# blues-hardware.net
KiCad netlist of a schematic drawn in EAGLE
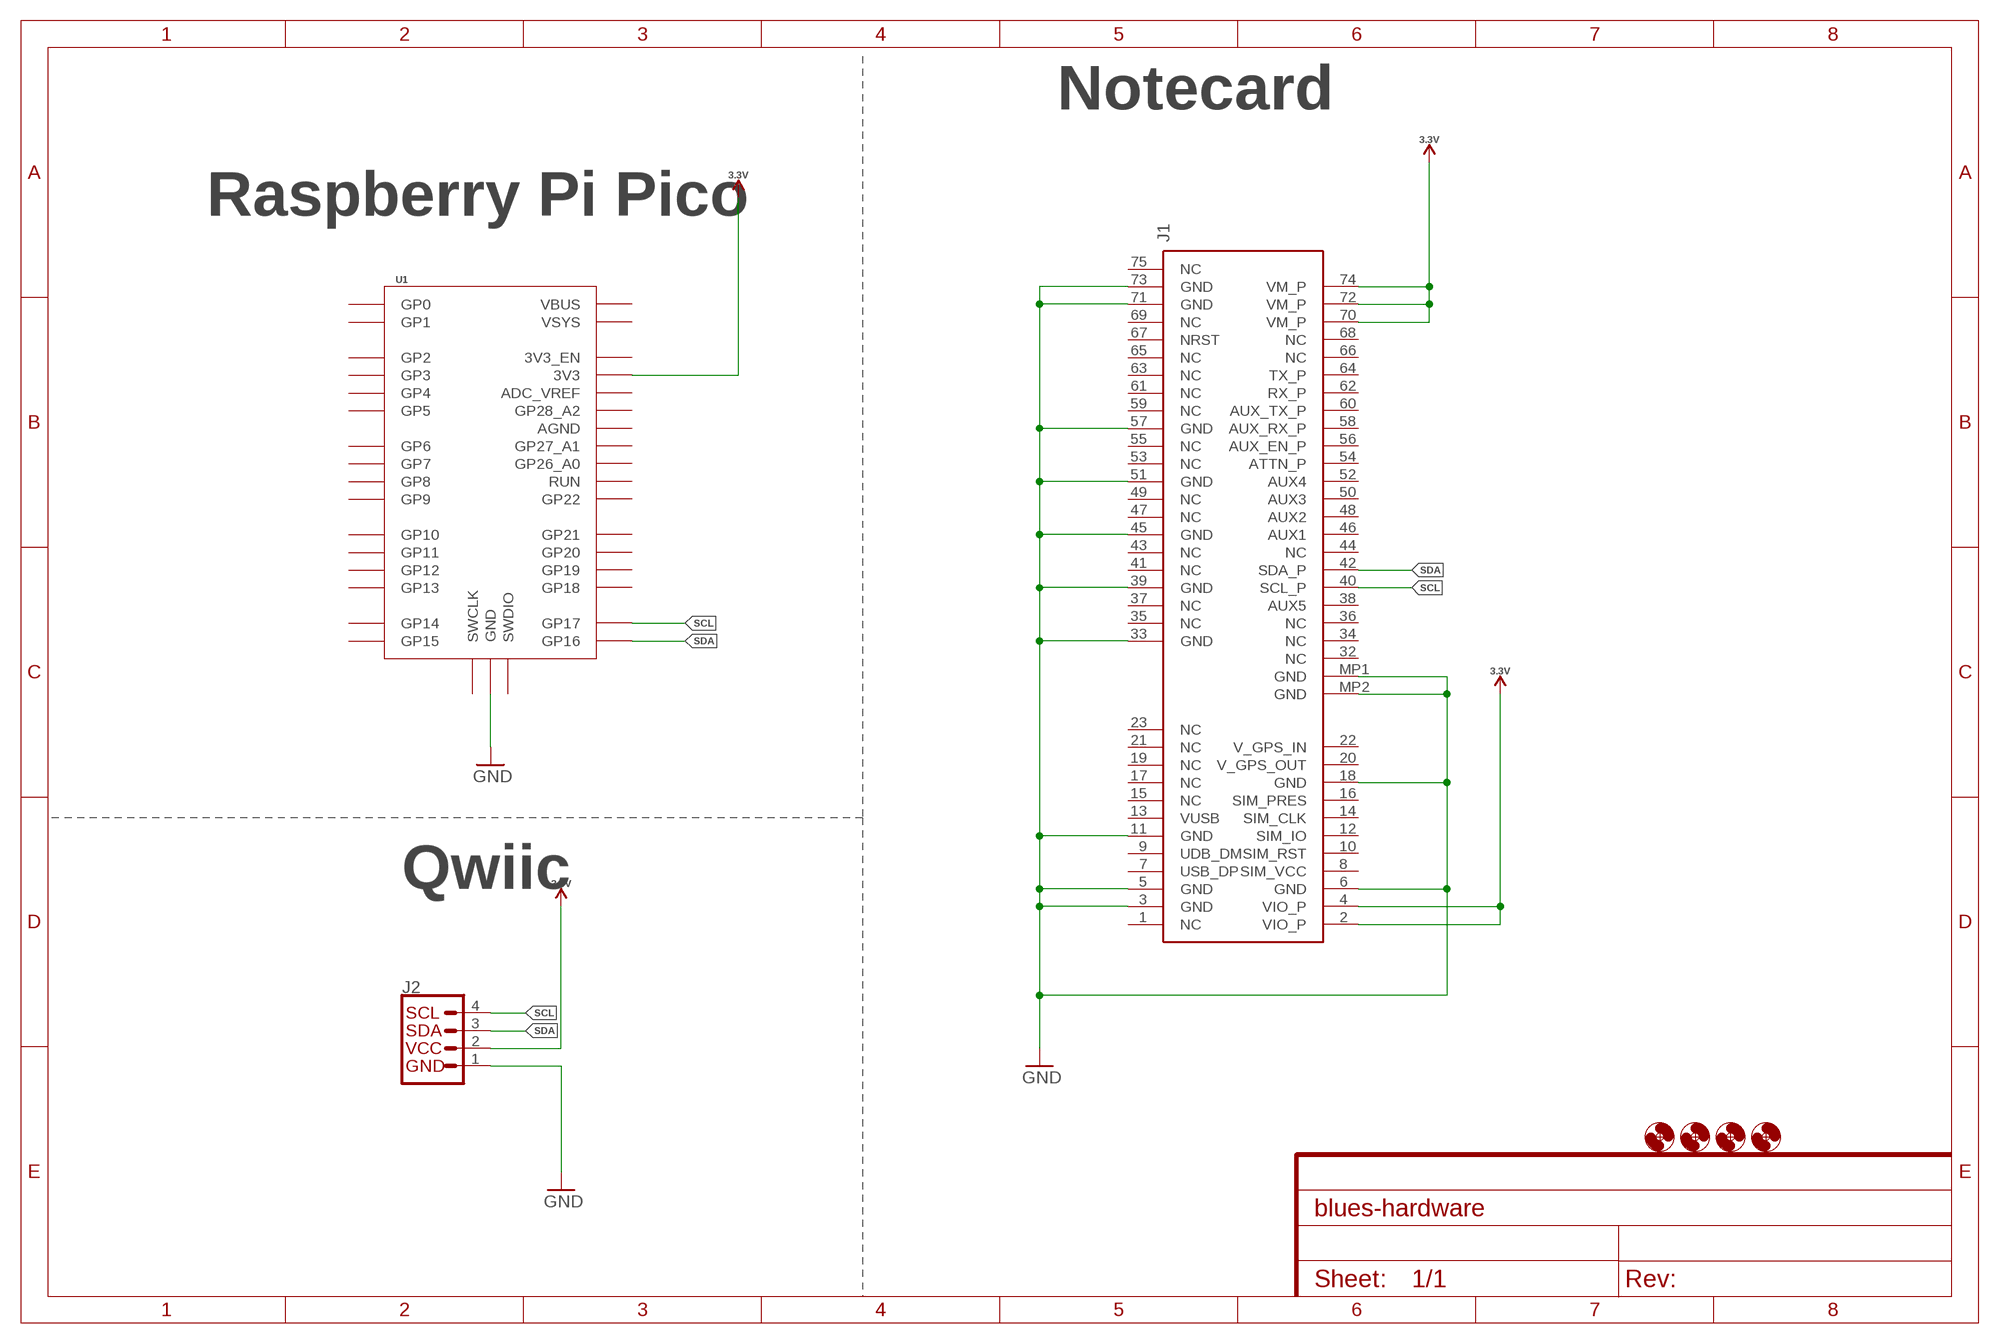
[diagram p0: schematic, sheet 1]

(export (version "E")
  (design (tool "Eeschema 10.0.6"))
  (components
    (comp (ref "H1")
      (value "MOUNT-HOLE3.0")
      (footprint "eagle-import:3,0")
      (libsource (lib "eagle-import") (part "MOUNT-HOLE3.0"))
    )
    (comp (ref "H2")
      (value "MOUNT-HOLE3.0")
      (footprint "eagle-import:3,0")
      (libsource (lib "eagle-import") (part "MOUNT-HOLE3.0"))
    )
    (comp (ref "H3")
      (value "MOUNT-HOLE3.0")
      (footprint "eagle-import:3,0")
      (libsource (lib "eagle-import") (part "MOUNT-HOLE3.0"))
    )
    (comp (ref "H4")
      (value "MOUNT-HOLE3.0")
      (footprint "eagle-import:3,0")
      (libsource (lib "eagle-import") (part "MOUNT-HOLE3.0"))
    )
    (comp (ref "J1")
      (value "MDT420E01001NOTECARD")
      (footprint "eagle-import:NOTECARD")
      (libsource (lib "eagle-import") (part "MDT420E01001NOTECARD"))
    )
    (comp (ref "J2")
      (value "QWIIC_CONNECTORJS-1MM")
      (footprint "eagle-import:1X04_1MM_RA")
      (libsource (lib "eagle-import") (part "QWIIC_CONNECTORJS-1MM"))
    )
    (comp (ref "U1")
      (value "RPI_PICO-TH")
      (footprint "eagle-import:RPI_PICO_TH")
      (libsource (lib "eagle-import") (part "RPI_PICO-TH"))
    )
  )
  (nets
    (net (code "1") (name "3.3V") (class "Default")
      (node (ref "J1") (pin "2") (pinfunction "VIO_P_2") (pintype "bidirectional"))
      (node (ref "J1") (pin "4") (pinfunction "VIO_P_4") (pintype "bidirectional"))
      (node (ref "J1") (pin "70") (pinfunction "VM_P_70") (pintype "bidirectional"))
      (node (ref "J1") (pin "72") (pinfunction "VM_P_72") (pintype "bidirectional"))
      (node (ref "J1") (pin "74") (pinfunction "VM_P_74") (pintype "bidirectional"))
      (node (ref "J2") (pin "2") (pinfunction "2_2") (pintype "power_in"))
      (node (ref "U1") (pin "3V3") (pinfunction "3V3_3V3") (pintype "bidirectional"))
    )
    (net (code "2") (name "GND") (class "Default")
      (node (ref "J1") (pin "11") (pinfunction "GND_11") (pintype "bidirectional"))
      (node (ref "J1") (pin "18") (pinfunction "GND_18") (pintype "bidirectional"))
      (node (ref "J1") (pin "3") (pinfunction "GND_3") (pintype "bidirectional"))
      (node (ref "J1") (pin "33") (pinfunction "GND_33") (pintype "bidirectional"))
      (node (ref "J1") (pin "39") (pinfunction "GND_39") (pintype "bidirectional"))
      (node (ref "J1") (pin "45") (pinfunction "GND_45") (pintype "bidirectional"))
      (node (ref "J1") (pin "5") (pinfunction "GND_5") (pintype "bidirectional"))
      (node (ref "J1") (pin "51") (pinfunction "GND_51") (pintype "bidirectional"))
      (node (ref "J1") (pin "57") (pinfunction "GND_57") (pintype "bidirectional"))
      (node (ref "J1") (pin "6") (pinfunction "GND_6") (pintype "bidirectional"))
      (node (ref "J1") (pin "71") (pinfunction "GND_71") (pintype "bidirectional"))
      (node (ref "J1") (pin "73") (pinfunction "GND_73") (pintype "bidirectional"))
      (node (ref "J1") (pin "MP1") (pinfunction "GND_MP1") (pintype "power_in"))
      (node (ref "J1") (pin "MP2") (pinfunction "GND_MP2") (pintype "bidirectional"))
      (node (ref "J2") (pin "1") (pinfunction "1_1") (pintype "power_in"))
      (node (ref "U1") (pin "GND@1") (pinfunction "GND_GND@1") (pintype "bidirectional"))
      (node (ref "U1") (pin "GND@2") (pinfunction "GND_GND@2") (pintype "bidirectional"))
      (node (ref "U1") (pin "GND@3") (pinfunction "GND_GND@3") (pintype "bidirectional"))
      (node (ref "U1") (pin "GND@4") (pinfunction "GND_GND@4") (pintype "bidirectional"))
      (node (ref "U1") (pin "GND@5") (pinfunction "GND_GND@5") (pintype "bidirectional"))
      (node (ref "U1") (pin "GND@6") (pinfunction "GND_GND@6") (pintype "bidirectional"))
      (node (ref "U1") (pin "GND@7") (pinfunction "GND_GND@7") (pintype "bidirectional"))
      (node (ref "U1") (pin "GND@8") (pinfunction "GND_GND@8") (pintype "bidirectional"))
    )
    (net (code "3") (name "SCL") (class "Default")
      (node (ref "J1") (pin "40") (pinfunction "SCL_P_40") (pintype "bidirectional"))
      (node (ref "J2") (pin "4") (pinfunction "4_4") (pintype "passive"))
      (node (ref "U1") (pin "GP17") (pinfunction "GP17_GP17") (pintype "bidirectional"))
    )
    (net (code "4") (name "SDA") (class "Default")
      (node (ref "J1") (pin "42") (pinfunction "SDA_P_42") (pintype "bidirectional"))
      (node (ref "J2") (pin "3") (pinfunction "3_3") (pintype "passive"))
      (node (ref "U1") (pin "GP16") (pinfunction "GP16_GP16") (pintype "bidirectional"))
    )
    (net (code "5") (name "unconnected-(J1-ATTN_P-Pad54)") (class "Default")
      (node (ref "J1") (pin "54") (pinfunction "ATTN_P_54") (pintype "bidirectional"))
    )
    (net (code "6") (name "unconnected-(J1-AUX1-Pad46)") (class "Default")
      (node (ref "J1") (pin "46") (pinfunction "AUX1_46") (pintype "bidirectional"))
    )
    (net (code "7") (name "unconnected-(J1-AUX2-Pad48)") (class "Default")
      (node (ref "J1") (pin "48") (pinfunction "AUX2_48") (pintype "bidirectional"))
    )
    (net (code "8") (name "unconnected-(J1-AUX3-Pad50)") (class "Default")
      (node (ref "J1") (pin "50") (pinfunction "AUX3_50") (pintype "bidirectional"))
    )
    (net (code "9") (name "unconnected-(J1-AUX4-Pad52)") (class "Default")
      (node (ref "J1") (pin "52") (pinfunction "AUX4_52") (pintype "bidirectional"))
    )
    (net (code "10") (name "unconnected-(J1-AUX5-Pad38)") (class "Default")
      (node (ref "J1") (pin "38") (pinfunction "AUX5_38") (pintype "bidirectional"))
    )
    (net (code "11") (name "unconnected-(J1-AUX_EN_P-Pad56)") (class "Default")
      (node (ref "J1") (pin "56") (pinfunction "AUX_EN_P_56") (pintype "bidirectional"))
    )
    (net (code "12") (name "unconnected-(J1-AUX_RX_P-Pad58)") (class "Default")
      (node (ref "J1") (pin "58") (pinfunction "AUX_RX_P_58") (pintype "bidirectional"))
    )
    (net (code "13") (name "unconnected-(J1-AUX_TX_P-Pad60)") (class "Default")
      (node (ref "J1") (pin "60") (pinfunction "AUX_TX_P_60") (pintype "bidirectional"))
    )
    (net (code "14") (name "unconnected-(J1-NC-Pad1)") (class "Default")
      (node (ref "J1") (pin "1") (pinfunction "NC_1") (pintype "bidirectional"))
    )
    (net (code "15") (name "unconnected-(J1-NC-Pad15)") (class "Default")
      (node (ref "J1") (pin "15") (pinfunction "NC_15") (pintype "bidirectional"))
    )
    (net (code "16") (name "unconnected-(J1-NC-Pad17)") (class "Default")
      (node (ref "J1") (pin "17") (pinfunction "NC_17") (pintype "bidirectional"))
    )
    (net (code "17") (name "unconnected-(J1-NC-Pad19)") (class "Default")
      (node (ref "J1") (pin "19") (pinfunction "NC_19") (pintype "bidirectional"))
    )
    (net (code "18") (name "unconnected-(J1-NC-Pad21)") (class "Default")
      (node (ref "J1") (pin "21") (pinfunction "NC_21") (pintype "bidirectional"))
    )
    (net (code "19") (name "unconnected-(J1-NC-Pad23)") (class "Default")
      (node (ref "J1") (pin "23") (pinfunction "NC_23") (pintype "bidirectional"))
    )
    (net (code "20") (name "unconnected-(J1-NC-Pad32)") (class "Default")
      (node (ref "J1") (pin "32") (pinfunction "NC_32") (pintype "bidirectional"))
    )
    (net (code "21") (name "unconnected-(J1-NC-Pad34)") (class "Default")
      (node (ref "J1") (pin "34") (pinfunction "NC_34") (pintype "bidirectional"))
    )
    (net (code "22") (name "unconnected-(J1-NC-Pad35)") (class "Default")
      (node (ref "J1") (pin "35") (pinfunction "NC_35") (pintype "bidirectional"))
    )
    (net (code "23") (name "unconnected-(J1-NC-Pad36)") (class "Default")
      (node (ref "J1") (pin "36") (pinfunction "NC_36") (pintype "bidirectional"))
    )
    (net (code "24") (name "unconnected-(J1-NC-Pad37)") (class "Default")
      (node (ref "J1") (pin "37") (pinfunction "NC_37") (pintype "bidirectional"))
    )
    (net (code "25") (name "unconnected-(J1-NC-Pad41)") (class "Default")
      (node (ref "J1") (pin "41") (pinfunction "NC_41") (pintype "bidirectional"))
    )
    (net (code "26") (name "unconnected-(J1-NC-Pad43)") (class "Default")
      (node (ref "J1") (pin "43") (pinfunction "NC_43") (pintype "bidirectional"))
    )
    (net (code "27") (name "unconnected-(J1-NC-Pad44)") (class "Default")
      (node (ref "J1") (pin "44") (pinfunction "NC_44") (pintype "bidirectional"))
    )
    (net (code "28") (name "unconnected-(J1-NC-Pad47)") (class "Default")
      (node (ref "J1") (pin "47") (pinfunction "NC_47") (pintype "bidirectional"))
    )
    (net (code "29") (name "unconnected-(J1-NC-Pad49)") (class "Default")
      (node (ref "J1") (pin "49") (pinfunction "NC_49") (pintype "bidirectional"))
    )
    (net (code "30") (name "unconnected-(J1-NC-Pad53)") (class "Default")
      (node (ref "J1") (pin "53") (pinfunction "NC_53") (pintype "bidirectional"))
    )
    (net (code "31") (name "unconnected-(J1-NC-Pad55)") (class "Default")
      (node (ref "J1") (pin "55") (pinfunction "NC_55") (pintype "bidirectional"))
    )
    (net (code "32") (name "unconnected-(J1-NC-Pad59)") (class "Default")
      (node (ref "J1") (pin "59") (pinfunction "NC_59") (pintype "bidirectional"))
    )
    (net (code "33") (name "unconnected-(J1-NC-Pad61)") (class "Default")
      (node (ref "J1") (pin "61") (pinfunction "NC_61") (pintype "bidirectional"))
    )
    (net (code "34") (name "unconnected-(J1-NC-Pad63)") (class "Default")
      (node (ref "J1") (pin "63") (pinfunction "NC_63") (pintype "bidirectional"))
    )
    (net (code "35") (name "unconnected-(J1-NC-Pad65)") (class "Default")
      (node (ref "J1") (pin "65") (pinfunction "NC_65") (pintype "bidirectional"))
    )
    (net (code "36") (name "unconnected-(J1-NC-Pad66)") (class "Default")
      (node (ref "J1") (pin "66") (pinfunction "NC_66") (pintype "bidirectional"))
    )
    (net (code "37") (name "unconnected-(J1-NC-Pad68)") (class "Default")
      (node (ref "J1") (pin "68") (pinfunction "NC_68") (pintype "bidirectional"))
    )
    (net (code "38") (name "unconnected-(J1-NC-Pad69)") (class "Default")
      (node (ref "J1") (pin "69") (pinfunction "NC_69") (pintype "bidirectional"))
    )
    (net (code "39") (name "unconnected-(J1-NC-Pad75)") (class "Default")
      (node (ref "J1") (pin "75") (pinfunction "NC_75") (pintype "bidirectional"))
    )
    (net (code "40") (name "unconnected-(J1-NRST-Pad67)") (class "Default")
      (node (ref "J1") (pin "67") (pinfunction "NRST_67") (pintype "bidirectional"))
    )
    (net (code "41") (name "unconnected-(J1-RX_P-Pad62)") (class "Default")
      (node (ref "J1") (pin "62") (pinfunction "RX_P_62") (pintype "bidirectional"))
    )
    (net (code "42") (name "unconnected-(J1-SIM_CLK-Pad14)") (class "Default")
      (node (ref "J1") (pin "14") (pinfunction "SIM_CLK_14") (pintype "bidirectional"))
    )
    (net (code "43") (name "unconnected-(J1-SIM_IO-Pad12)") (class "Default")
      (node (ref "J1") (pin "12") (pinfunction "SIM_IO_12") (pintype "bidirectional"))
    )
    (net (code "44") (name "unconnected-(J1-SIM_PRES-Pad16)") (class "Default")
      (node (ref "J1") (pin "16") (pinfunction "SIM_PRES_16") (pintype "bidirectional"))
    )
    (net (code "45") (name "unconnected-(J1-SIM_RST-Pad10)") (class "Default")
      (node (ref "J1") (pin "10") (pinfunction "SIM_RST_10") (pintype "bidirectional"))
    )
    (net (code "46") (name "unconnected-(J1-SIM_VCC-Pad8)") (class "Default")
      (node (ref "J1") (pin "8") (pinfunction "SIM_VCC_8") (pintype "bidirectional"))
    )
    (net (code "47") (name "unconnected-(J1-TX_P-Pad64)") (class "Default")
      (node (ref "J1") (pin "64") (pinfunction "TX_P_64") (pintype "bidirectional"))
    )
    (net (code "48") (name "unconnected-(J1-UDB_DM-Pad9)") (class "Default")
      (node (ref "J1") (pin "9") (pinfunction "UDB_DM_9") (pintype "bidirectional"))
    )
    (net (code "49") (name "unconnected-(J1-USB_DP-Pad7)") (class "Default")
      (node (ref "J1") (pin "7") (pinfunction "USB_DP_7") (pintype "bidirectional"))
    )
    (net (code "50") (name "unconnected-(J1-VUSB-Pad13)") (class "Default")
      (node (ref "J1") (pin "13") (pinfunction "VUSB_13") (pintype "bidirectional"))
    )
    (net (code "51") (name "unconnected-(J1-V_GPS_IN-Pad22)") (class "Default")
      (node (ref "J1") (pin "22") (pinfunction "V_GPS_IN_22") (pintype "bidirectional"))
    )
    (net (code "52") (name "unconnected-(J1-V_GPS_OUT-Pad20)") (class "Default")
      (node (ref "J1") (pin "20") (pinfunction "V_GPS_OUT_20") (pintype "bidirectional"))
    )
    (net (code "53") (name "unconnected-(U1-Pad3V3_EN)") (class "Default")
      (node (ref "U1") (pin "3V3_EN") (pinfunction "3V3_EN_3V3_EN") (pintype "bidirectional"))
    )
    (net (code "54") (name "unconnected-(U1-PadADC_VREF)") (class "Default")
      (node (ref "U1") (pin "ADC_VREF") (pinfunction "ADC_VREF_ADC_VREF") (pintype "bidirectional"))
    )
    (net (code "55") (name "unconnected-(U1-PadAGND)") (class "Default")
      (node (ref "U1") (pin "AGND") (pinfunction "AGND_AGND") (pintype "bidirectional"))
    )
    (net (code "56") (name "unconnected-(U1-PadGP0)") (class "Default")
      (node (ref "U1") (pin "GP0") (pinfunction "GP0_GP0") (pintype "bidirectional"))
    )
    (net (code "57") (name "unconnected-(U1-PadGP1)") (class "Default")
      (node (ref "U1") (pin "GP1") (pinfunction "GP1_GP1") (pintype "bidirectional"))
    )
    (net (code "58") (name "unconnected-(U1-PadGP2)") (class "Default")
      (node (ref "U1") (pin "GP2") (pinfunction "GP2_GP2") (pintype "bidirectional"))
    )
    (net (code "59") (name "unconnected-(U1-PadGP3)") (class "Default")
      (node (ref "U1") (pin "GP3") (pinfunction "GP3_GP3") (pintype "bidirectional"))
    )
    (net (code "60") (name "unconnected-(U1-PadGP4)") (class "Default")
      (node (ref "U1") (pin "GP4") (pinfunction "GP4_GP4") (pintype "bidirectional"))
    )
    (net (code "61") (name "unconnected-(U1-PadGP5)") (class "Default")
      (node (ref "U1") (pin "GP5") (pinfunction "GP5_GP5") (pintype "bidirectional"))
    )
    (net (code "62") (name "unconnected-(U1-PadGP6)") (class "Default")
      (node (ref "U1") (pin "GP6") (pinfunction "GP6_GP6") (pintype "bidirectional"))
    )
    (net (code "63") (name "unconnected-(U1-PadGP7)") (class "Default")
      (node (ref "U1") (pin "GP7") (pinfunction "GP7_GP7") (pintype "bidirectional"))
    )
    (net (code "64") (name "unconnected-(U1-PadGP8)") (class "Default")
      (node (ref "U1") (pin "GP8") (pinfunction "GP8_GP8") (pintype "bidirectional"))
    )
    (net (code "65") (name "unconnected-(U1-PadGP9)") (class "Default")
      (node (ref "U1") (pin "GP9") (pinfunction "GP9_GP9") (pintype "bidirectional"))
    )
    (net (code "66") (name "unconnected-(U1-PadGP10)") (class "Default")
      (node (ref "U1") (pin "GP10") (pinfunction "GP10_GP10") (pintype "bidirectional"))
    )
    (net (code "67") (name "unconnected-(U1-PadGP11)") (class "Default")
      (node (ref "U1") (pin "GP11") (pinfunction "GP11_GP11") (pintype "bidirectional"))
    )
    (net (code "68") (name "unconnected-(U1-PadGP12)") (class "Default")
      (node (ref "U1") (pin "GP12") (pinfunction "GP12_GP12") (pintype "bidirectional"))
    )
    (net (code "69") (name "unconnected-(U1-PadGP13)") (class "Default")
      (node (ref "U1") (pin "GP13") (pinfunction "GP13_GP13") (pintype "bidirectional"))
    )
    (net (code "70") (name "unconnected-(U1-PadGP14)") (class "Default")
      (node (ref "U1") (pin "GP14") (pinfunction "GP14_GP14") (pintype "bidirectional"))
    )
    (net (code "71") (name "unconnected-(U1-PadGP15)") (class "Default")
      (node (ref "U1") (pin "GP15") (pinfunction "GP15_GP15") (pintype "bidirectional"))
    )
    (net (code "72") (name "unconnected-(U1-PadGP18)") (class "Default")
      (node (ref "U1") (pin "GP18") (pinfunction "GP18_GP18") (pintype "bidirectional"))
    )
    (net (code "73") (name "unconnected-(U1-PadGP19)") (class "Default")
      (node (ref "U1") (pin "GP19") (pinfunction "GP19_GP19") (pintype "bidirectional"))
    )
    (net (code "74") (name "unconnected-(U1-PadGP20)") (class "Default")
      (node (ref "U1") (pin "GP20") (pinfunction "GP20_GP20") (pintype "bidirectional"))
    )
    (net (code "75") (name "unconnected-(U1-PadGP21)") (class "Default")
      (node (ref "U1") (pin "GP21") (pinfunction "GP21_GP21") (pintype "bidirectional"))
    )
    (net (code "76") (name "unconnected-(U1-PadGP22)") (class "Default")
      (node (ref "U1") (pin "GP22") (pinfunction "GP22_GP22") (pintype "bidirectional"))
    )
    (net (code "77") (name "unconnected-(U1-PadGP26_A0)") (class "Default")
      (node (ref "U1") (pin "GP26_A0") (pinfunction "GP26_A0_GP26_A0") (pintype "bidirectional"))
    )
    (net (code "78") (name "unconnected-(U1-PadGP27_A1)") (class "Default")
      (node (ref "U1") (pin "GP27_A1") (pinfunction "GP27_A1_GP27_A1") (pintype "bidirectional"))
    )
    (net (code "79") (name "unconnected-(U1-PadGP28_A2)") (class "Default")
      (node (ref "U1") (pin "GP28_A2") (pinfunction "GP28_A2_GP28_A2") (pintype "bidirectional"))
    )
    (net (code "80") (name "unconnected-(U1-PadRUN)") (class "Default")
      (node (ref "U1") (pin "RUN") (pinfunction "RUN_RUN") (pintype "bidirectional"))
    )
    (net (code "81") (name "unconnected-(U1-PadSWCLK)") (class "Default")
      (node (ref "U1") (pin "SWCLK") (pinfunction "SWCLK_SWCLK") (pintype "bidirectional"))
    )
    (net (code "82") (name "unconnected-(U1-PadSWDIO)") (class "Default")
      (node (ref "U1") (pin "SWDIO") (pinfunction "SWDIO_SWDIO") (pintype "bidirectional"))
    )
    (net (code "83") (name "unconnected-(U1-PadVBUS)") (class "Default")
      (node (ref "U1") (pin "VBUS") (pinfunction "VBUS_VBUS") (pintype "bidirectional"))
    )
    (net (code "84") (name "unconnected-(U1-PadVSYS)") (class "Default")
      (node (ref "U1") (pin "VSYS") (pinfunction "VSYS_VSYS") (pintype "bidirectional"))
    )
  )
)
